# benzinPWM_v1.net
KiCad netlist of a schematic drawn in EAGLE
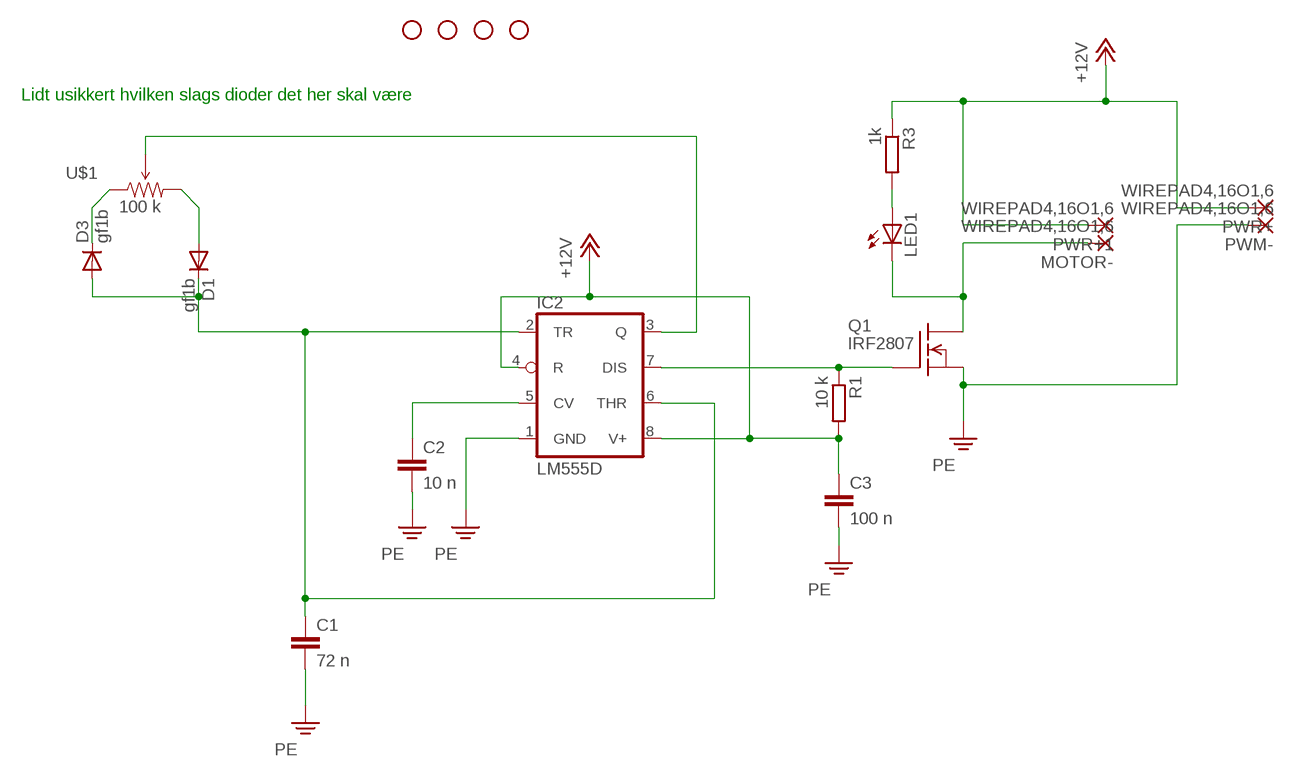
[diagram p0: schematic, sheet 1]

(export (version "E")
  (design (tool "Eeschema 10.0.6"))
  (components
    (comp (ref "C1")
      (value "72 n")
      (footprint "eagle-import:C0805")
      (libsource (lib "eagle-import") (part "C-EUC0805"))
    )
    (comp (ref "C2")
      (value "10 n")
      (footprint "eagle-import:C0805")
      (libsource (lib "eagle-import") (part "C-EUC0805"))
    )
    (comp (ref "C3")
      (value "100 n")
      (footprint "eagle-import:C0805")
      (libsource (lib "eagle-import") (part "C-EUC0805"))
    )
    (comp (ref "D1")
      (value "gf1b")
      (footprint "eagle-import:GF1")
      (libsource (lib "eagle-import") (part "DIODE-GF1"))
    )
    (comp (ref "D3")
      (value "gf1b")
      (footprint "eagle-import:GF1")
      (libsource (lib "eagle-import") (part "DIODE-GF1"))
    )
    (comp (ref "IC2")
      (value "LM555D")
      (footprint "eagle-import:SO08")
      (libsource (lib "eagle-import") (part "555DLM"))
    )
    (comp (ref "JP3")
      (value "STAND-OFF")
      (footprint "eagle-import:STAND-OFF")
      (libsource (lib "eagle-import") (part "STAND-OFF"))
    )
    (comp (ref "JP4")
      (value "STAND-OFF")
      (footprint "eagle-import:STAND-OFF")
      (libsource (lib "eagle-import") (part "STAND-OFF"))
    )
    (comp (ref "JP5")
      (value "STAND-OFF")
      (footprint "eagle-import:STAND-OFF")
      (libsource (lib "eagle-import") (part "STAND-OFF"))
    )
    (comp (ref "JP6")
      (value "STAND-OFF")
      (footprint "eagle-import:STAND-OFF")
      (libsource (lib "eagle-import") (part "STAND-OFF"))
    )
    (comp (ref "LED1")
      (value "LEDCHIPLED_0805")
      (footprint "eagle-import:CHIPLED_0805")
      (libsource (lib "eagle-import") (part "LEDCHIPLED_0805"))
    )
    (comp (ref "MOTOR-")
      (value "WIREPAD4,16O1,6")
      (footprint "eagle-import:4,16O1,6")
      (libsource (lib "eagle-import") (part "WIREPAD4,16O1,6"))
    )
    (comp (ref "PWM-")
      (value "WIREPAD4,16O1,6")
      (footprint "eagle-import:4,16O1,6")
      (libsource (lib "eagle-import") (part "WIREPAD4,16O1,6"))
    )
    (comp (ref "PWR+")
      (value "WIREPAD4,16O1,6")
      (footprint "eagle-import:4,16O1,6")
      (libsource (lib "eagle-import") (part "WIREPAD4,16O1,6"))
    )
    (comp (ref "PWR+1")
      (value "WIREPAD4,16O1,6")
      (footprint "eagle-import:4,16O1,6")
      (libsource (lib "eagle-import") (part "WIREPAD4,16O1,6"))
    )
    (comp (ref "Q1")
      (value "IRF2807")
      (footprint "eagle-import:TO220")
      (libsource (lib "eagle-import") (part "IRF510"))
    )
    (comp (ref "R1")
      (value "10 k")
      (footprint "eagle-import:M0805")
      (libsource (lib "eagle-import") (part "R-EU_M0805"))
    )
    (comp (ref "R3")
      (value "1k")
      (footprint "eagle-import:M0805")
      (libsource (lib "eagle-import") (part "R-EU_M0805"))
    )
    (comp (ref "U$1")
      (value "100 k")
      (footprint "eagle-import:3362U-2")
      (libsource (lib "eagle-import") (part "TRIMPOT"))
    )
  )
  (nets
    (net (code "1") (name "+12V") (class "Default")
      (node (ref "C3") (pin "1") (pinfunction "1_1") (pintype "passive"))
      (node (ref "IC2") (pin "4") (pinfunction "R_4") (pintype "input"))
      (node (ref "IC2") (pin "8") (pinfunction "V+_8") (pintype "power_in"))
      (node (ref "PWR+") (pin "1") (pinfunction "P_1") (pintype "passive"))
      (node (ref "PWR+1") (pin "1") (pinfunction "P_1") (pintype "passive"))
      (node (ref "R1") (pin "2") (pinfunction "2_2") (pintype "passive"))
      (node (ref "R3") (pin "1") (pinfunction "1_1") (pintype "passive"))
    )
    (net (code "2") (name "Net-(IC2-CV)") (class "Default")
      (node (ref "C2") (pin "1") (pinfunction "1_1") (pintype "passive"))
      (node (ref "IC2") (pin "5") (pinfunction "CV_5") (pintype "input"))
    )
    (net (code "3") (name "Net-(IC2-DIS)") (class "Default")
      (node (ref "IC2") (pin "7") (pinfunction "DIS_7") (pintype "input"))
      (node (ref "Q1") (pin "1") (pinfunction "G_1") (pintype "passive"))
      (node (ref "R1") (pin "1") (pinfunction "1_1") (pintype "passive"))
    )
    (net (code "4") (name "Net-(IC2-Q)") (class "Default")
      (node (ref "IC2") (pin "3") (pinfunction "Q_3") (pintype "output"))
      (node (ref "U$1") (pin "2") (pinfunction "WIPER_2") (pintype "passive"))
    )
    (net (code "5") (name "Net-(IC2-THR)") (class "Default")
      (node (ref "C1") (pin "1") (pinfunction "1_1") (pintype "passive"))
      (node (ref "D1") (pin "C") (pinfunction "C_C") (pintype "passive"))
      (node (ref "D3") (pin "A") (pinfunction "A_A") (pintype "passive"))
      (node (ref "IC2") (pin "2") (pinfunction "TR_2") (pintype "input"))
      (node (ref "IC2") (pin "6") (pinfunction "THR_6") (pintype "input"))
    )
    (net (code "6") (name "Net-(LED1-PadA)") (class "Default")
      (node (ref "LED1") (pin "A") (pinfunction "A_A") (pintype "passive"))
      (node (ref "R3") (pin "2") (pinfunction "2_2") (pintype "passive"))
    )
    (net (code "7") (name "Net-(MOTOR--P)") (class "Default")
      (node (ref "LED1") (pin "C") (pinfunction "C_C") (pintype "passive"))
      (node (ref "MOTOR-") (pin "1") (pinfunction "P_1") (pintype "passive"))
      (node (ref "Q1") (pin "2") (pinfunction "D_2") (pintype "passive"))
    )
    (net (code "8") (name "Net-(U$1-CCW)") (class "Default")
      (node (ref "D3") (pin "C") (pinfunction "C_C") (pintype "passive"))
      (node (ref "U$1") (pin "1") (pinfunction "CCW_1") (pintype "passive"))
    )
    (net (code "9") (name "Net-(U$1-CW)") (class "Default")
      (node (ref "D1") (pin "A") (pinfunction "A_A") (pintype "passive"))
      (node (ref "U$1") (pin "3") (pinfunction "CW_3") (pintype "passive"))
    )
    (net (code "10") (name "PE") (class "Default")
      (node (ref "C1") (pin "2") (pinfunction "2_2") (pintype "passive"))
      (node (ref "C2") (pin "2") (pinfunction "2_2") (pintype "passive"))
      (node (ref "C3") (pin "2") (pinfunction "2_2") (pintype "passive"))
      (node (ref "IC2") (pin "1") (pinfunction "GND_1") (pintype "power_in"))
      (node (ref "PWM-") (pin "1") (pinfunction "P_1") (pintype "passive"))
      (node (ref "Q1") (pin "3") (pinfunction "S_3") (pintype "passive"))
    )
  )
)
